# Supply.net
KiCad netlist of a schematic drawn in Altium Designer
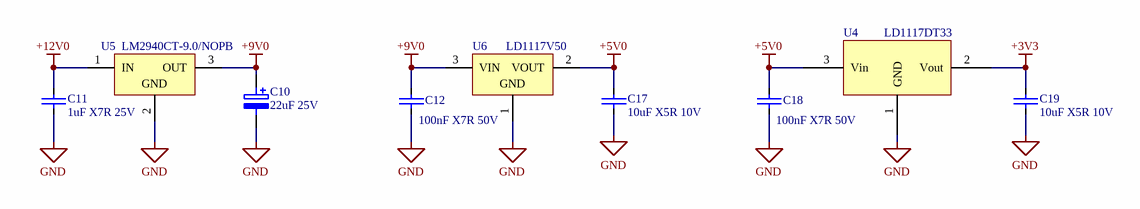
[diagram p0: Supply.SchDoc]

(export (version "E")
  (design (tool "Eeschema 10.0.6"))
  (components
    (comp (ref "C10")
      (value "22uF 25V")
      (footprint "TANT_D")
      (description "Capacità polarizzata")
      (fields
        (field (name "1 SUPPLIER PART NUMBER") "KETT491D226K025AT")
        (field (name "ARSILICII PART NUMBER") "CPC0352022")
      )
      (libsource (lib "Library_20-02-20") (part "CAP_TANT_22uF 25V Case D"))
    )
    (comp (ref "C11")
      (value "1uF X7R 25V")
      (footprint "0805")
      (description "Capacità")
      (fields
        (field (name "1 SUPPLIER PART NUMBER") "CL21B105KAFNNNG")
        (field (name "ARSILICII PART NUMBER") "CPC0212002")
      )
      (libsource (lib "Library_20-02-20") (part "CAP_1uF X7R 25V_0805"))
    )
    (comp (ref "C12")
      (value "100nF X7R 50V")
      (footprint "0805")
      (description "Capacità")
      (fields
        (field (name "1 SUPPLIER PART NUMBER") "C0805C104K5RAC7800")
        (field (name "2 SUPPLIER PART NUMBER") "08055C104KAT2A AVX")
      )
      (libsource (lib "Library_20-02-20") (part "CAP_100nF X7R 50V_0805"))
    )
    (comp (ref "C17")
      (value "10uF X5R 10V")
      (footprint "0805")
      (description "Capacità")
      (fields
        (field (name "1 SUPPLIER PART NUMBER") "CL21A106KPFNNNE")
        (field (name "ARSILICII PART NUMBER") "CPC0212010")
      )
      (libsource (lib "Library_20-02-20") (part "CAP_10uF X5R 10V_0805"))
    )
    (comp (ref "C18")
      (value "100nF X7R 50V")
      (footprint "0805")
      (description "Capacità")
      (fields
        (field (name "1 SUPPLIER PART NUMBER") "C0805C104K5RAC7800")
        (field (name "2 SUPPLIER PART NUMBER") "08055C104KAT2A AVX")
      )
      (libsource (lib "Library_20-02-20") (part "CAP_100nF X7R 50V_0805"))
    )
    (comp (ref "C19")
      (value "10uF X5R 10V")
      (footprint "0805")
      (description "Capacità")
      (fields
        (field (name "1 SUPPLIER PART NUMBER") "CL21A106KPFNNNE")
        (field (name "ARSILICII PART NUMBER") "CPC0212010")
      )
      (libsource (lib "Library_20-02-20") (part "CAP_10uF X5R 10V_0805"))
    )
    (comp (ref "U4")
      (value "LD1117DT33")
      (footprint "TO-252-7805")
      (description "Regolatore Low Dropout")
      (fields
        (field (name "1 SUPPLIER PART NUMBER") "LD1117DT33TR TO252-3")
        (field (name "ARSILICII PART NUMBER") "IC01000010")
      )
      (libsource (lib "Library_20-02-20") (part "LD1117DT33"))
    )
    (comp (ref "U5")
      (value "LM2940CT-9.0/NOPB")
      (footprint "NDE0003A")
      (description "1A Low Dropout Regulator, 3-pin TO-220, Pb-Free")
      (fields (field (name "MANUFACTURER") "Texas Instruments"))
      (libsource (lib "Altium Content Vault") (part "PM-REG-LM2940-SIL3"))
    )
    (comp (ref "U6")
      (value "LD1117V50")
      (footprint "TO220")
      (description "Fixed Low Drop Positive Voltage Regulator, 5V, 3-Pin TO-220")
      (libsource (lib "Altium Content Vault") (part "PM-REG-LD1117V-SIL3"))
    )
  )
  (nets
    (net (code "1") (name "+3V3") (class "Default")
      (node (ref "C19") (pin "1") (pintype "passive"))
      (node (ref "U4") (pin "2") (pinfunction "Vout_2") (pintype "power_in"))
    )
    (net (code "2") (name "+5V0") (class "Default")
      (node (ref "C17") (pin "1") (pintype "passive"))
      (node (ref "C18") (pin "1") (pintype "passive"))
      (node (ref "U4") (pin "3") (pinfunction "Vin_3") (pintype "power_in"))
      (node (ref "U6") (pin "2") (pinfunction "VOUT_2") (pintype "power_in"))
    )
    (net (code "3") (name "+9V0") (class "Default")
      (node (ref "C10") (pin "1") (pintype "passive"))
      (node (ref "C12") (pin "1") (pintype "passive"))
      (node (ref "U5") (pin "3") (pinfunction "OUT_3") (pintype "power_in"))
      (node (ref "U6") (pin "3") (pinfunction "VIN_3") (pintype "power_in"))
    )
    (net (code "4") (name "+12V0") (class "Default")
      (node (ref "C11") (pin "1") (pintype "passive"))
      (node (ref "U5") (pin "1") (pinfunction "IN_1") (pintype "power_in"))
    )
    (net (code "5") (name "GND") (class "Default")
      (node (ref "C10") (pin "2") (pintype "passive"))
      (node (ref "C11") (pin "2") (pintype "passive"))
      (node (ref "C12") (pin "2") (pintype "passive"))
      (node (ref "C17") (pin "2") (pintype "passive"))
      (node (ref "C18") (pin "2") (pintype "passive"))
      (node (ref "C19") (pin "2") (pintype "passive"))
      (node (ref "U4") (pin "1") (pinfunction "GND_1") (pintype "power_in"))
      (node (ref "U5") (pin "2") (pinfunction "GND_2") (pintype "power_in"))
      (node (ref "U6") (pin "1") (pinfunction "GND_1") (pintype "power_in"))
    )
  )
)
